# Nuio_Left_Keyboard_Rev_H_Power.net
KiCad netlist of a schematic drawn in Altium Designer
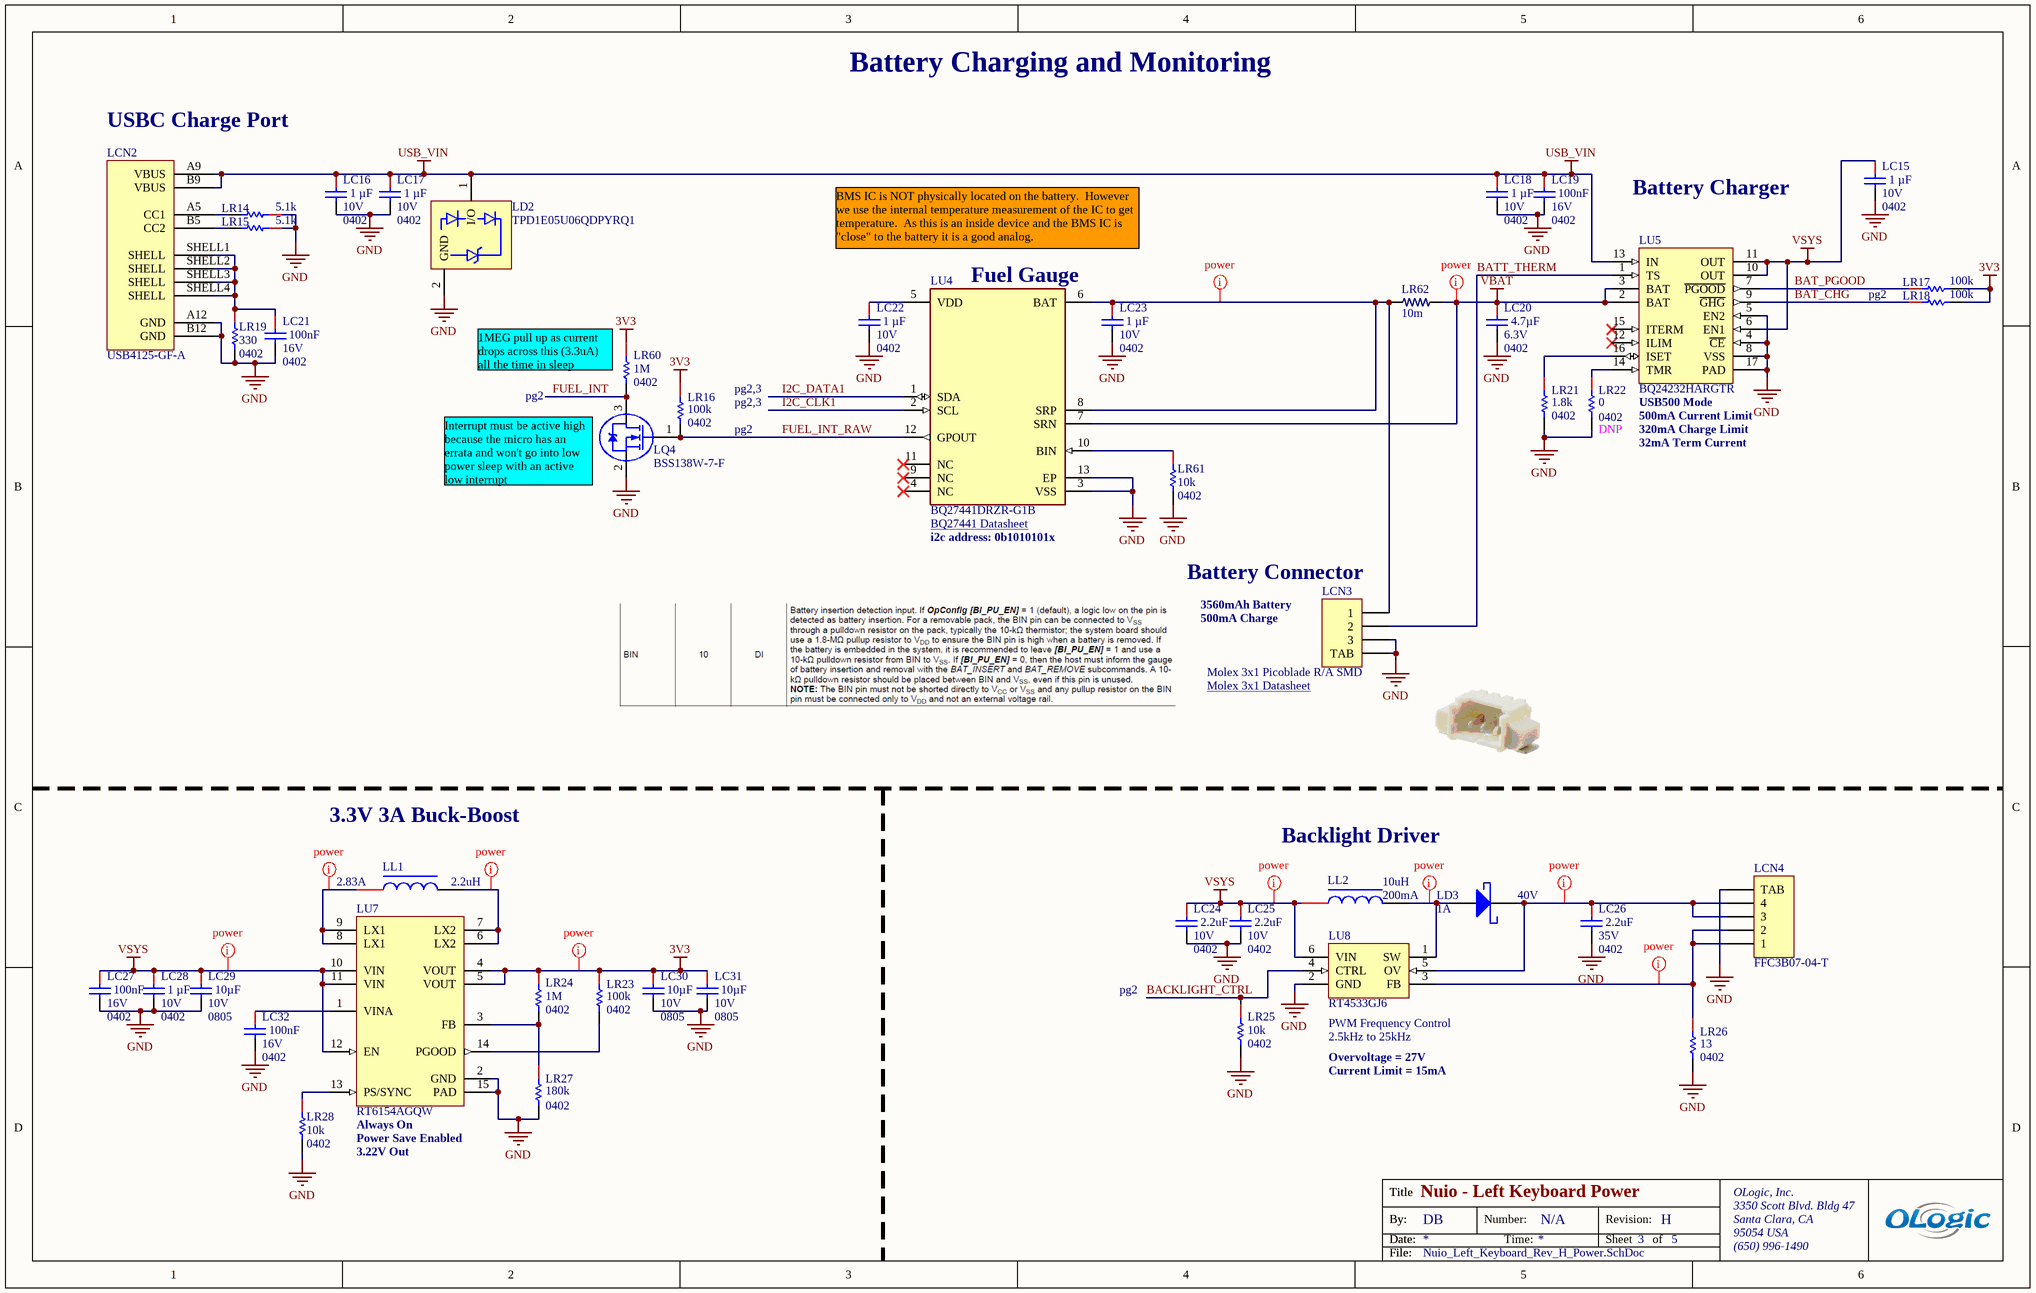
[diagram p0: Nuio_Left_Keyboard_Rev_H_Power.SchDoc]

(export (version "E")
  (design (tool "Eeschema 10.0.6"))
  (components
    (comp (ref "LC15")
      (value "CAP CER 1UF 10V X5R 0402")
      (footprint "CAPC0402(1005)_L")
      (description "±20% 10V Ceramic Capacitor X5R 0402 (1005 Metric)")
      (fields
        (field (name "PACKAGE (IMPERIAL)") "0402")
        (field (name "VOLTAGE (RATED)") "10V")
        (field (name "CAPACITANCE") "1 µF")
        (field (name "MANUFACTURER PART NUMBER") "CC0402MRX5R6BB105")
        (field (name "TOLERANCE") "±20%")
      )
      (libsource (lib "OLogic Nexus Vault") (part "OL_Capacitor"))
    )
    (comp (ref "LC16")
      (value "CAP CER 1UF 10V X5R 0402")
      (footprint "CAPC0402(1005)_L")
      (description "±20% 10V Ceramic Capacitor X5R 0402 (1005 Metric)")
      (fields
        (field (name "PACKAGE (IMPERIAL)") "0402")
        (field (name "VOLTAGE (RATED)") "10V")
        (field (name "CAPACITANCE") "1 µF")
        (field (name "MANUFACTURER PART NUMBER") "CC0402MRX5R6BB105")
        (field (name "TOLERANCE") "±20%")
      )
      (libsource (lib "OLogic Nexus Vault") (part "OL_Capacitor"))
    )
    (comp (ref "LC17")
      (value "CAP CER 1UF 10V X5R 0402")
      (footprint "CAPC0402(1005)_L")
      (description "±20% 10V Ceramic Capacitor X5R 0402 (1005 Metric)")
      (fields
        (field (name "PACKAGE (IMPERIAL)") "0402")
        (field (name "VOLTAGE (RATED)") "10V")
        (field (name "CAPACITANCE") "1 µF")
        (field (name "MANUFACTURER PART NUMBER") "CC0402MRX5R6BB105")
        (field (name "TOLERANCE") "±20%")
      )
      (libsource (lib "OLogic Nexus Vault") (part "OL_Capacitor"))
    )
    (comp (ref "LC18")
      (value "CAP CER 1UF 10V X5R 0402")
      (footprint "CAPC0402(1005)_L")
      (description "±20% 10V Ceramic Capacitor X5R 0402 (1005 Metric)")
      (fields
        (field (name "PACKAGE (IMPERIAL)") "0402")
        (field (name "VOLTAGE (RATED)") "10V")
        (field (name "CAPACITANCE") "1 µF")
        (field (name "MANUFACTURER PART NUMBER") "CC0402MRX5R6BB105")
        (field (name "TOLERANCE") "±20%")
      )
      (libsource (lib "OLogic Nexus Vault") (part "OL_Capacitor"))
    )
    (comp (ref "LC19")
      (value "CAP CER 0.1UF 16V X5R 0402")
      (footprint "CAPC0402(1005)_L")
      (description "±10% 16V Ceramic Capacitor X5R 0402 (1005 Metric)")
      (fields
        (field (name "PACKAGE (IMPERIAL)") "0402")
        (field (name "VOLTAGE (RATED)") "16V")
        (field (name "CAPACITANCE") "100nF")
        (field (name "MANUFACTURER") "Taiyo Yuden")
        (field (name "MANUFACTURER PART NUMBER") "EMK105BJ104KV-F")
      )
      (libsource (lib "OLogic Nexus Vault") (part "OL_Capacitor"))
    )
    (comp (ref "LC20")
      (value "4.7uF")
      (footprint "CAPC0402(1005)_L")
      (description "CAP CER 4.7UF 6.3V 10% X5R 0402")
      (fields
        (field (name "PACKAGE (IMPERIAL)") "0402")
        (field (name "VOLTAGE (RATED)") "6.3V")
        (field (name "CAPACITANCE") "4.7µF")
        (field (name "TOLERANCE") "20%")
      )
      (libsource (lib "OLogic Nexus Vault") (part "OL_Capacitor"))
    )
    (comp (ref "LC21")
      (value "CAP CER 0.1UF 16V X5R 0402")
      (footprint "CAPC0402(1005)_L")
      (description "±10% 16V Ceramic Capacitor X5R 0402 (1005 Metric)")
      (fields
        (field (name "PACKAGE (IMPERIAL)") "0402")
        (field (name "VOLTAGE (RATED)") "16V")
        (field (name "CAPACITANCE") "100nF")
        (field (name "MANUFACTURER") "Taiyo Yuden")
        (field (name "MANUFACTURER PART NUMBER") "EMK105BJ104KV-F")
      )
      (libsource (lib "OLogic Nexus Vault") (part "OL_Capacitor"))
    )
    (comp (ref "LC22")
      (value "CAP CER 1UF 10V X5R 0402")
      (footprint "CAPC0402(1005)_L")
      (description "±20% 10V Ceramic Capacitor X5R 0402 (1005 Metric)")
      (fields
        (field (name "PACKAGE (IMPERIAL)") "0402")
        (field (name "VOLTAGE (RATED)") "10V")
        (field (name "CAPACITANCE") "1 µF")
        (field (name "MANUFACTURER PART NUMBER") "CC0402MRX5R6BB105")
        (field (name "TOLERANCE") "±20%")
      )
      (libsource (lib "OLogic Nexus Vault") (part "OL_Capacitor"))
    )
    (comp (ref "LC23")
      (value "CAP CER 1UF 10V X5R 0402")
      (footprint "CAPC0402(1005)_L")
      (description "±20% 10V Ceramic Capacitor X5R 0402 (1005 Metric)")
      (fields
        (field (name "PACKAGE (IMPERIAL)") "0402")
        (field (name "VOLTAGE (RATED)") "10V")
        (field (name "CAPACITANCE") "1 µF")
        (field (name "MANUFACTURER PART NUMBER") "CC0402MRX5R6BB105")
        (field (name "TOLERANCE") "±20%")
      )
      (libsource (lib "OLogic Nexus Vault") (part "OL_Capacitor"))
    )
    (comp (ref "LC24")
      (value "CAP CER 2.2UF 10V X5R 0402")
      (footprint "CAPC0402(1005)_L")
      (description "±20% 10V Ceramic Capacitor X5R 0402 (1005 Metric)")
      (fields
        (field (name "PACKAGE (IMPERIAL)") "0402")
        (field (name "VOLTAGE (RATED)") "10V")
        (field (name "CAPACITANCE") "2.2uF")
        (field (name "TOLERANCE") "20%")
        (field (name "MANUFACTURER") "KEMET")
      )
      (libsource (lib "OLogic Nexus Vault") (part "OL_Capacitor"))
    )
    (comp (ref "LC25")
      (value "CAP CER 2.2UF 10V X5R 0402")
      (footprint "CAPC0402(1005)_L")
      (description "±20% 10V Ceramic Capacitor X5R 0402 (1005 Metric)")
      (fields
        (field (name "PACKAGE (IMPERIAL)") "0402")
        (field (name "VOLTAGE (RATED)") "10V")
        (field (name "CAPACITANCE") "2.2uF")
        (field (name "TOLERANCE") "20%")
        (field (name "MANUFACTURER") "KEMET")
      )
      (libsource (lib "OLogic Nexus Vault") (part "OL_Capacitor"))
    )
    (comp (ref "LC26")
      (value "2.2uF")
      (footprint "CAPC0402(1005)_L")
      (description "CAP CER 2.2UF 35V 10% X5R 0402")
      (fields
        (field (name "VOLTAGE (RATED)") "35V")
        (field (name "PACKAGE (IMPERIAL)") "0402")
        (field (name "TOLERANCE") "10%")
      )
      (libsource (lib "OLogic Nexus Vault") (part "=Capacitance"))
    )
    (comp (ref "LC27")
      (value "CAP CER 0.1UF 16V X5R 0402")
      (footprint "CAPC0402(1005)_L")
      (description "±10% 16V Ceramic Capacitor X5R 0402 (1005 Metric)")
      (fields
        (field (name "PACKAGE (IMPERIAL)") "0402")
        (field (name "VOLTAGE (RATED)") "16V")
        (field (name "CAPACITANCE") "100nF")
        (field (name "MANUFACTURER") "Taiyo Yuden")
        (field (name "MANUFACTURER PART NUMBER") "EMK105BJ104KV-F")
      )
      (libsource (lib "OLogic Nexus Vault") (part "OL_Capacitor"))
    )
    (comp (ref "LC28")
      (value "CAP CER 1UF 10V X5R 0402")
      (footprint "CAPC0402(1005)_L")
      (description "±20% 10V Ceramic Capacitor X5R 0402 (1005 Metric)")
      (fields
        (field (name "PACKAGE (IMPERIAL)") "0402")
        (field (name "VOLTAGE (RATED)") "10V")
        (field (name "CAPACITANCE") "1 µF")
        (field (name "MANUFACTURER PART NUMBER") "CC0402MRX5R6BB105")
        (field (name "TOLERANCE") "±20%")
      )
      (libsource (lib "OLogic Nexus Vault") (part "OL_Capacitor"))
    )
    (comp (ref "LC29")
      (value "CAP CER 10UF 10V X7R 0805")
      (footprint "CAPC0805(2012)_L")
      (description "10µF ±10% 10V Ceramic Capacitor X7R 0805 (2012 Metric)")
      (fields
        (field (name "VOLTAGE (RATED)") "10V")
        (field (name "PACKAGE (IMPERIAL)") "0805")
        (field (name "CAPACITANCE") "10µF")
        (field (name "TOLERANCE") "10%")
        (field (name "MANUFACTURER PART NUMBER") "GRM21BR71A106KA73K")
      )
      (libsource (lib "OLogic Nexus Vault") (part "OL_Capacitor"))
    )
    (comp (ref "LC30")
      (value "CAP CER 10UF 10V X7R 0805")
      (footprint "CAPC0805(2012)_L")
      (description "10µF ±10% 10V Ceramic Capacitor X7R 0805 (2012 Metric)")
      (fields
        (field (name "VOLTAGE (RATED)") "10V")
        (field (name "PACKAGE (IMPERIAL)") "0805")
        (field (name "CAPACITANCE") "10µF")
        (field (name "TOLERANCE") "10%")
        (field (name "MANUFACTURER PART NUMBER") "GRM21BR71A106KA73K")
      )
      (libsource (lib "OLogic Nexus Vault") (part "OL_Capacitor"))
    )
    (comp (ref "LC31")
      (value "CAP CER 10UF 10V X7R 0805")
      (footprint "CAPC0805(2012)_L")
      (description "10µF ±10% 10V Ceramic Capacitor X7R 0805 (2012 Metric)")
      (fields
        (field (name "VOLTAGE (RATED)") "10V")
        (field (name "PACKAGE (IMPERIAL)") "0805")
        (field (name "CAPACITANCE") "10µF")
        (field (name "TOLERANCE") "10%")
        (field (name "MANUFACTURER PART NUMBER") "GRM21BR71A106KA73K")
      )
      (libsource (lib "OLogic Nexus Vault") (part "OL_Capacitor"))
    )
    (comp (ref "LC32")
      (value "CAP CER 0.1UF 16V X5R 0402")
      (footprint "CAPC0402(1005)_L")
      (description "±10% 16V Ceramic Capacitor X5R 0402 (1005 Metric)")
      (fields
        (field (name "PACKAGE (IMPERIAL)") "0402")
        (field (name "VOLTAGE (RATED)") "16V")
        (field (name "CAPACITANCE") "100nF")
        (field (name "MANUFACTURER") "Taiyo Yuden")
        (field (name "MANUFACTURER PART NUMBER") "EMK105BJ104KV-F")
      )
      (libsource (lib "OLogic Nexus Vault") (part "OL_Capacitor"))
    )
    (comp (ref "LCN2")
      (value "USB4125-GF-A")
      (footprint "USB4125-GF-A")
      (fields (field (name "MANUFACTURER") "GCT") (field (name "VOLTAGE") "20V"))
      (libsource (lib "OLogic Nexus Vault") (part "USB4125-GF-A"))
    )
    (comp (ref "LCN3")
      (value "Molex 3x1 Picoblade R/A SMD")
      (footprint "Molex 3x1 Picoblade R_A SMD")
      (description "1.25mm (.049\") Pitch PicoBlade Header, Surface Mount, Right Angle, Lead-free, 3 Circuits")
      (libsource (lib "Nuio_Left_Keyboard_Rev_G") (part "CMP-00344-01"))
    )
    (comp (ref "LCN4")
      (value "FFC3B07-04-T")
      (footprint "FFC3B07-04-T")
      (fields (field (name "MANUFACTURER") "GCT"))
      (libsource (lib "OLogic Nexus Vault") (part "FFC3B07-04-T"))
    )
    (comp (ref "LD2")
      (value "TPD1E05U06QDPYRQ1")
      (footprint "FP-DPY0002A-MFG")
      (description "TVS DIODE 5.5V 14V 2X1SON")
      (fields (field (name "MANUFACTURER") "Texas Instruments"))
      (libsource (lib "OLogic Nexus Vault") (part "TPD1E05U06QDPYRQ1"))
    )
    (comp (ref "LD3")
      (value "PMEG4010AESBYL")
      (footprint "PMEG4010AESBYL-Footprint-1")
      (description "DIODE SCHOTTKY 40V 1A SOD993")
      (fields (field (name "DC REVERSE VOLTAGE MAX") "40V") (field (name "CURRENT AVG RECTIFIED") "1A"))
      (libsource (lib "OLogic Nexus Vault") (part "PMEG4010AESB"))
    )
    (comp (ref "LL1")
      (value "FIXED IND 2.2UH 2.83A 74MOHM SMD")
      (footprint "FIXED IND 2.2UH 2.83A 74MOHM SMD")
      (description "2.2 µH Shielded Wirewound Inductor 2.83 A 74mOhm Max Nonstandard -")
      (fields
        (field (name "INDUCTANCE") "2.2uH")
        (field (name "CURRENT RATING (AMPS)") "2.83A")
        (field (name "MANUFACTURER") "TDK Corporation")
      )
      (libsource (lib "OLogic Nexus Vault") (part "OL_Inductor"))
    )
    (comp (ref "LL2")
      (value "10uH")
      (footprint "FIXED IND 10UH 300MA 680MOHM SMD")
      (description "10 µH Shielded Multilayer Inductor 300 mA 680mOhm 0805 (2012 Metric)")
      (fields
        (field (name "MANUFACTURER PART NUMBER") "MLZ2012M100HT000")
        (field (name "TOLERANCE") "20%")
        (field (name "SATURATION CURRENT") "200mA")
      )
      (libsource (lib "OLogic Nexus Vault") (part "OL_Inductor"))
    )
    (comp (ref "LQ4")
      (value "BSS138W-7-F")
      (footprint "DIOD-SOT323-3_V")
      (description "DIODES INC. - BSS138W-7-F. - BSS FAMILY SOT323 T&R 3K ROHS COMPLIANT: YES")
      (fields (field (name "VOLTAGE") "50V") (field (name "POWER") "200mW"))
      (libsource (lib "Nuio_Left_Keyboard_Rev_H") (part "CMP-00300-01"))
    )
    (comp (ref "LR14")
      (value "RES SMD 5.1K OHM 1% 1/10W 0402")
      (footprint "RESC0402(1005)_L")
      (description "5.1 kOhms ±1% 0.1W, 1/10W Chip Resistor 0402 (1005 Metric) Automotive AEC-Q200 Thick Film")
      (fields
        (field (name "RESISTANCE") "5.1k")
        (field (name "POWER") "63mW")
        (field (name "TOLERANCE") "1%")
      )
      (libsource (lib "OLogic Nexus Vault") (part "=Resistance"))
    )
    (comp (ref "LR15")
      (value "RES SMD 5.1K OHM 1% 1/10W 0402")
      (footprint "RESC0402(1005)_L")
      (description "5.1 kOhms ±1% 0.1W, 1/10W Chip Resistor 0402 (1005 Metric) Automotive AEC-Q200 Thick Film")
      (fields
        (field (name "RESISTANCE") "5.1k")
        (field (name "POWER") "63mW")
        (field (name "TOLERANCE") "1%")
      )
      (libsource (lib "OLogic Nexus Vault") (part "=Resistance"))
    )
    (comp (ref "LR16")
      (value "100k")
      (footprint "RESC0402(1005)_L")
      (description "±1% 0.063W, 1/16W Chip Resistor 0402 (1005 Metric) Moisture Resistant Thick Film")
      (fields
        (field (name "CASE CODE (IMPERIAL)") "0402")
        (field (name "TOLERANCE") "1%")
        (field (name "MANUFACTURER") "YAGEO")
      )
      (libsource (lib "OLogic Nexus Vault") (part "=Resistance"))
    )
    (comp (ref "LR17")
      (value "100k")
      (footprint "RESC0402(1005)_L")
      (description "±1% 0.063W, 1/16W Chip Resistor 0402 (1005 Metric) Moisture Resistant Thick Film")
      (fields (field (name "TOLERANCE") "1%") (field (name "MANUFACTURER") "YAGEO"))
      (libsource (lib "OLogic Nexus Vault") (part "=Resistance"))
    )
    (comp (ref "LR18")
      (value "100k")
      (footprint "RESC0402(1005)_L")
      (description "±1% 0.063W, 1/16W Chip Resistor 0402 (1005 Metric) Moisture Resistant Thick Film")
      (fields (field (name "TOLERANCE") "1%") (field (name "MANUFACTURER") "YAGEO"))
      (libsource (lib "OLogic Nexus Vault") (part "=Resistance"))
    )
    (comp (ref "LR19")
      (value "RES SMD 330 OHM 1% 1/16W 0402")
      (footprint "RESC0402(1005)_L")
      (description "330 Ohms ±1% 0.063W, 1/16W Chip Resistor 0402 (1005 Metric) Automotive AEC-Q200 Thick Film")
      (fields
        (field (name "RESISTANCE") "330")
        (field (name "PACKAGE (IMPERIAL)") "0402")
        (field (name "POWER") "63mW")
        (field (name "TOLERANCE") "1%")
      )
      (libsource (lib "OLogic Nexus Vault") (part "OL_Resistor"))
    )
    (comp (ref "LR21")
      (value "1.8k")
      (footprint "RESC0402(1005)_L")
      (description "1.8 kOhms ±0.1% 0.063W, 1/16W Chip Resistor 0402 (1005 Metric) Automotive AEC-Q200 Thin Film")
      (fields
        (field (name "TOLERANCE") "0.1%")
        (field (name "CASE CODE (IMPERIAL)") "0402")
        (field (name "MANUFACTURER") "Panasonic Electronic Components")
      )
      (libsource (lib "OLogic Nexus Vault") (part "=Resistance"))
    )
    (comp (ref "LR22")
      (value "RES 0 OHM JUMPER 1/16W 0402")
      (footprint "RESC0402(1005)_L")
      (description "0 Ohms Jumper Chip Resistor 0402 (1005 Metric) Automotive AEC-Q200 Thick Film")
      (fields
        (field (name "PACKAGE (IMPERIAL)") "0402")
        (field (name "RESISTANCE") "0")
        (field (name "POWER") "63mW")
        (field (name "TOLERANCE") "0%")
      )
      (libsource (lib "OLogic Nexus Vault") (part "=Resistance"))
    )
    (comp (ref "LR23")
      (value "100k")
      (footprint "RESC0402(1005)_L")
      (description "±1% 0.063W, 1/16W Chip Resistor 0402 (1005 Metric) Moisture Resistant Thick Film")
      (fields
        (field (name "CASE CODE (IMPERIAL)") "0402")
        (field (name "TOLERANCE") "1%")
        (field (name "MANUFACTURER") "YAGEO")
      )
      (libsource (lib "OLogic Nexus Vault") (part "=Resistance"))
    )
    (comp (ref "LR24")
      (value "RES 1M OHM 1% 1/16W 0402")
      (footprint "RESC0402(1005)_L")
      (description "1 MOhms ±1% 0.063W, 1/16W Chip Resistor 0402 (1005 Metric) Moisture Resistant Thick Film")
      (fields
        (field (name "RESISTANCE") "1M")
        (field (name "CASE/PACKAGE") "0402")
        (field (name "MANUFACTURER") "YAGEO")
        (field (name "MANUFACTURER PART NUMBER") "RC0402FR-071ML")
      )
      (libsource (lib "OLogic Nexus Vault") (part "OL_Resistor"))
    )
    (comp (ref "LR25")
      (value "RES SMD 10K OHM 1% 1/16W 0402")
      (footprint "RESC0402_YAGEO")
      (fields
        (field (name "RESISTANCE") "10k")
        (field (name "PACKAGE (IMPERIAL)") "0402")
        (field (name "MANUFACTURER") "Yageo")
        (field (name "TOLERANCE") "1%")
        (field (name "MANUFACTURER PART NUMBER") "AT0402FRE0710KL")
      )
      (libsource (lib "OLogic Nexus Vault") (part "OL_Resistor"))
    )
    (comp (ref "LR26")
      (value "13")
      (footprint "RESC0402(1005)_L")
      (description "SMD Chip Resistor, 13 Ohm, ± 1%, 63 mW, 0402 [1005 Metric], Thick Film, General Purpose")
      (fields (field (name "TOLERANCE") "1%") (field (name "CASE/PACKAGE") "0402"))
      (libsource (lib "Nuio_Left_Keyboard_Rev_G") (part "CMP-001-2304-01"))
    )
    (comp (ref "LR27")
      (value "180k")
      (footprint "RESC0402(1005)_L")
      (description "RES 180K OHM 1% 1/16W 0402")
      (fields
        (field (name "PACKAGE (IMPERIAL)") "0402")
        (field (name "POWER") "63mW")
        (field (name "TOLERANCE") "1%")
        (field (name "RESISTANCE") "180k")
      )
      (libsource (lib "OLogic Nexus Vault") (part "=Resistance"))
    )
    (comp (ref "LR28")
      (value "RES SMD 10K OHM 1% 1/16W 0402")
      (footprint "RESC0402_YAGEO")
      (fields
        (field (name "RESISTANCE") "10k")
        (field (name "PACKAGE (IMPERIAL)") "0402")
        (field (name "MANUFACTURER") "Yageo")
        (field (name "TOLERANCE") "1%")
        (field (name "MANUFACTURER PART NUMBER") "AT0402FRE0710KL")
      )
      (libsource (lib "OLogic Nexus Vault") (part "OL_Resistor"))
    )
    (comp (ref "LR60")
      (value "RES 1M OHM 1% 1/16W 0402")
      (footprint "RESC0402(1005)_L")
      (description "1 MOhms ±1% 0.063W, 1/16W Chip Resistor 0402 (1005 Metric) Moisture Resistant Thick Film")
      (fields
        (field (name "RESISTANCE") "1M")
        (field (name "CASE/PACKAGE") "0402")
        (field (name "MANUFACTURER") "YAGEO")
        (field (name "MANUFACTURER PART NUMBER") "RC0402FR-071ML")
      )
      (libsource (lib "OLogic Nexus Vault") (part "OL_Resistor"))
    )
    (comp (ref "LR61")
      (value "RES SMD 10K OHM 1% 1/16W 0402")
      (footprint "RESC0402_YAGEO")
      (fields
        (field (name "RESISTANCE") "10k")
        (field (name "PACKAGE (IMPERIAL)") "0402")
        (field (name "MANUFACTURER") "Yageo")
        (field (name "TOLERANCE") "1%")
        (field (name "MANUFACTURER PART NUMBER") "AT0402FRE0710KL")
      )
      (libsource (lib "OLogic Nexus Vault") (part "OL_Resistor"))
    )
    (comp (ref "LR62")
      (value "10m")
      (footprint "0805 PACKAGE")
      (description "10mOhm 0805 Resistor 1%")
      (libsource (lib "Resistor 0805 1P") (part "10m 0805 Resistor 1%_1"))
    )
    (comp (ref "LU4")
      (value "BQ27441DRZR-G1B")
      (footprint "Nuio_Left_Keyboard_Rev_H:FP-DRZ0012A-MFG")
      (description "IC BATT FUEL GAUGE LI-ION 12SON")
      (libsource (lib "Nuio_Left_Keyboard_Rev_H") (part "CMP-04911-000067-1"))
    )
    (comp (ref "LU5")
      (value "BQ24232HARGTR")
      (footprint "BQ24232HARGTR")
      (description "USB Friendly 0.5A Li-ion charger with power-Path, 10.5V OVP 16-VQFN -5 to 125")
      (libsource (lib "Nuio_Left_Keyboard_Rev_G") (part "CMP-001-1983-03"))
    )
    (comp (ref "LU7")
      (value "RT6154AGQW")
      (footprint "PSON50P300X80_HS-15N")
      (description "IC REG BCK BST ADJ 4A 14WDFN")
      (fields (field (name "MANUFACTURER") "Richtek USA Inc."))
      (libsource (lib "OLogic Nexus Vault") (part "RT6154AGQW"))
    )
    (comp (ref "LU8")
      (value "RT4533GJ6")
      (footprint "RT4533GJ6")
      (description "IC LED DRVR RGLTR PWM TSOT23-6")
      (libsource (lib "OLogic Nexus Vault") (part "RT4533GJ6"))
    )
  )
  (nets
    (net (code "1") (name "/BACKLIGHT_CTRL") (class "Default")
      (node (ref "LR25") (pin "1") (pinfunction "1_1") (pintype "passive"))
      (node (ref "LU8") (pin "4") (pinfunction "CTRL_4") (pintype "input"))
    )
    (net (code "2") (name "/BATT_THERM") (class "Default")
      (node (ref "LCN3") (pin "2") (pinfunction "2_2") (pintype "passive"))
      (node (ref "LU5") (pin "1") (pinfunction "TS_1") (pintype "input"))
    )
    (net (code "3") (name "/BAT_CHG") (class "Default")
      (node (ref "LR18") (pin "1") (pinfunction "1_1") (pintype "passive"))
      (node (ref "LU5") (pin "9") (pinfunction "~{GHG}_9") (pintype "output"))
    )
    (net (code "4") (name "/BAT_PGOOD") (class "Default")
      (node (ref "LR17") (pin "1") (pinfunction "1_1") (pintype "passive"))
      (node (ref "LU5") (pin "7") (pinfunction "~{PGOOD}_7") (pintype "output"))
    )
    (net (code "5") (name "/FUEL_INT") (class "Default")
      (node (ref "LQ4") (pin "3") (pinfunction "D_3") (pintype "passive"))
      (node (ref "LR60") (pin "2") (pinfunction "2_2") (pintype "passive"))
    )
    (net (code "6") (name "/FUEL_INT_RAW") (class "Default")
      (node (ref "LQ4") (pin "1") (pinfunction "G_1") (pintype "passive"))
      (node (ref "LR16") (pin "2") (pinfunction "2_2") (pintype "passive"))
      (node (ref "LU4") (pin "12") (pinfunction "GPOUT_12") (pintype "output"))
    )
    (net (code "7") (name "/I2C_CLK1") (class "Default")
      (node (ref "LU4") (pin "2") (pinfunction "SCL_2") (pintype "input"))
    )
    (net (code "8") (name "/I2C_DATA1") (class "Default")
      (node (ref "LU4") (pin "1") (pinfunction "SDA_1") (pintype "bidirectional"))
    )
    (net (code "9") (name "3V3") (class "Default")
      (node (ref "LC30") (pin "1") (pinfunction "1_1") (pintype "passive"))
      (node (ref "LC31") (pin "1") (pinfunction "1_1") (pintype "passive"))
      (node (ref "LR16") (pin "1") (pinfunction "1_1") (pintype "passive"))
      (node (ref "LR17") (pin "2") (pinfunction "2_2") (pintype "passive"))
      (node (ref "LR18") (pin "2") (pinfunction "2_2") (pintype "passive"))
      (node (ref "LR23") (pin "1") (pinfunction "1_1") (pintype "passive"))
      (node (ref "LR24") (pin "1") (pinfunction "1_1") (pintype "passive"))
      (node (ref "LR60") (pin "1") (pinfunction "1_1") (pintype "passive"))
      (node (ref "LU7") (pin "4") (pinfunction "VOUT_4") (pintype "power_in"))
      (node (ref "LU7") (pin "5") (pinfunction "VOUT_5") (pintype "power_in"))
    )
    (net (code "10") (name "GND") (class "Default")
      (node (ref "LC15") (pin "2") (pinfunction "2_2") (pintype "passive"))
      (node (ref "LC16") (pin "2") (pinfunction "2_2") (pintype "passive"))
      (node (ref "LC17") (pin "2") (pinfunction "2_2") (pintype "passive"))
      (node (ref "LC18") (pin "2") (pinfunction "2_2") (pintype "passive"))
      (node (ref "LC19") (pin "2") (pinfunction "2_2") (pintype "passive"))
      (node (ref "LC20") (pin "2") (pinfunction "2_2") (pintype "passive"))
      (node (ref "LC21") (pin "2") (pinfunction "2_2") (pintype "passive"))
      (node (ref "LC22") (pin "2") (pinfunction "2_2") (pintype "passive"))
      (node (ref "LC23") (pin "2") (pinfunction "2_2") (pintype "passive"))
      (node (ref "LC24") (pin "2") (pinfunction "2_2") (pintype "passive"))
      (node (ref "LC25") (pin "2") (pinfunction "2_2") (pintype "passive"))
      (node (ref "LC26") (pin "2") (pinfunction "2_2") (pintype "passive"))
      (node (ref "LC27") (pin "2") (pinfunction "2_2") (pintype "passive"))
      (node (ref "LC28") (pin "2") (pinfunction "2_2") (pintype "passive"))
      (node (ref "LC29") (pin "2") (pinfunction "2_2") (pintype "passive"))
      (node (ref "LC30") (pin "2") (pinfunction "2_2") (pintype "passive"))
      (node (ref "LC31") (pin "2") (pinfunction "2_2") (pintype "passive"))
      (node (ref "LC32") (pin "2") (pinfunction "2_2") (pintype "passive"))
      (node (ref "LCN2") (pin "A12") (pinfunction "GND_A12") (pintype "passive"))
      (node (ref "LCN2") (pin "B12") (pinfunction "GND_B12") (pintype "passive"))
      (node (ref "LCN3") (pin "0") (pinfunction "TAB_0") (pintype "passive"))
      (node (ref "LCN3") (pin "3") (pinfunction "3_3") (pintype "passive"))
      (node (ref "LCN4") (pin "0") (pinfunction "TAB_0") (pintype "passive"))
      (node (ref "LD2") (pin "2") (pinfunction "GND_2") (pintype "passive"))
      (node (ref "LQ4") (pin "2") (pinfunction "S_2") (pintype "passive"))
      (node (ref "LR14") (pin "1") (pinfunction "1_1") (pintype "passive"))
      (node (ref "LR15") (pin "1") (pinfunction "1_1") (pintype "passive"))
      (node (ref "LR19") (pin "2") (pinfunction "2_2") (pintype "passive"))
      (node (ref "LR21") (pin "2") (pinfunction "2_2") (pintype "passive"))
      (node (ref "LR22") (pin "2") (pinfunction "2_2") (pintype "passive"))
      (node (ref "LR25") (pin "2") (pinfunction "2_2") (pintype "passive"))
      (node (ref "LR26") (pin "2") (pinfunction "2_2") (pintype "passive"))
      (node (ref "LR27") (pin "2") (pinfunction "2_2") (pintype "passive"))
      (node (ref "LR28") (pin "2") (pinfunction "2_2") (pintype "passive"))
      (node (ref "LR61") (pin "2") (pinfunction "2_2") (pintype "passive"))
      (node (ref "LU4") (pin "13") (pinfunction "EP_13") (pintype "passive"))
      (node (ref "LU4") (pin "3") (pinfunction "VSS_3") (pintype "power_in"))
      (node (ref "LU5") (pin "17") (pinfunction "PAD_17") (pintype "passive"))
      (node (ref "LU5") (pin "4") (pinfunction "~{CE}_4") (pintype "input"))
      (node (ref "LU5") (pin "5") (pinfunction "EN2_5") (pintype "input"))
      (node (ref "LU5") (pin "8") (pinfunction "VSS_8") (pintype "passive"))
      (node (ref "LU7") (pin "15") (pinfunction "PAD_15") (pintype "power_in"))
      (node (ref "LU7") (pin "2") (pinfunction "GND_2") (pintype "power_in"))
      (node (ref "LU8") (pin "2") (pinfunction "GND_2") (pintype "power_in"))
    )
    (net (code "11") (name "Net-(LC21-Pad1)") (class "Default")
      (node (ref "LC21") (pin "1") (pinfunction "1_1") (pintype "passive"))
      (node (ref "LCN2") (pin "SHELL1") (pinfunction "SHELL_SHELL1") (pintype "passive"))
      (node (ref "LCN2") (pin "SHELL2") (pinfunction "SHELL_SHELL2") (pintype "passive"))
      (node (ref "LCN2") (pin "SHELL3") (pinfunction "SHELL_SHELL3") (pintype "passive"))
      (node (ref "LCN2") (pin "SHELL4") (pinfunction "SHELL_SHELL4") (pintype "passive"))
      (node (ref "LR19") (pin "1") (pinfunction "1_1") (pintype "passive"))
    )
    (net (code "12") (name "Net-(LCN2-CC1)") (class "Default")
      (node (ref "LCN2") (pin "A5") (pinfunction "CC1_A5") (pintype "passive"))
      (node (ref "LR14") (pin "2") (pinfunction "2_2") (pintype "passive"))
    )
    (net (code "13") (name "Net-(LCN2-CC2)") (class "Default")
      (node (ref "LCN2") (pin "B5") (pinfunction "CC2_B5") (pintype "passive"))
      (node (ref "LR15") (pin "2") (pinfunction "2_2") (pintype "passive"))
    )
    (net (code "14") (name "Net-(LD3-A)") (class "Default")
      (node (ref "LD3") (pin "2") (pinfunction "A_2") (pintype "passive"))
      (node (ref "LL2") (pin "2") (pinfunction "2_2") (pintype "passive"))
      (node (ref "LU8") (pin "1") (pinfunction "SW_1") (pintype "passive"))
    )
    (net (code "15") (name "Net-(LD3-K)") (class "Default")
      (node (ref "LC26") (pin "1") (pinfunction "1_1") (pintype "passive"))
      (node (ref "LCN4") (pin "3") (pinfunction "3_3") (pintype "passive"))
      (node (ref "LCN4") (pin "4") (pinfunction "4_4") (pintype "passive"))
      (node (ref "LD3") (pin "1") (pinfunction "K_1") (pintype "passive"))
      (node (ref "LU8") (pin "5") (pinfunction "OV_5") (pintype "input"))
    )
    (net (code "16") (name "Net-(LL1-Pad1)") (class "Default")
      (node (ref "LL1") (pin "1") (pinfunction "1_1") (pintype "passive"))
      (node (ref "LU7") (pin "8") (pinfunction "LX1_8") (pintype "passive"))
      (node (ref "LU7") (pin "9") (pinfunction "LX1_9") (pintype "passive"))
    )
    (net (code "17") (name "Net-(LL1-Pad2)") (class "Default")
      (node (ref "LL1") (pin "2") (pinfunction "2_2") (pintype "passive"))
      (node (ref "LU7") (pin "6") (pinfunction "LX2_6") (pintype "passive"))
      (node (ref "LU7") (pin "7") (pinfunction "LX2_7") (pintype "passive"))
    )
    (net (code "18") (name "Net-(LU4-BAT)") (class "Default")
      (node (ref "LC23") (pin "1") (pinfunction "1_1") (pintype "passive"))
      (node (ref "LCN3") (pin "1") (pinfunction "1_1") (pintype "passive"))
      (node (ref "LR62") (pin "1") (pinfunction "1_1") (pintype "passive"))
      (node (ref "LU4") (pin "6") (pinfunction "BAT_6") (pintype "power_in"))
      (node (ref "LU4") (pin "8") (pinfunction "SRP_8") (pintype "passive"))
    )
    (net (code "19") (name "Net-(LU4-BIN)") (class "Default")
      (node (ref "LR61") (pin "1") (pinfunction "1_1") (pintype "passive"))
      (node (ref "LU4") (pin "10") (pinfunction "BIN_10") (pintype "input"))
    )
    (net (code "20") (name "Net-(LU4-VDD)") (class "Default")
      (node (ref "LC22") (pin "1") (pinfunction "1_1") (pintype "passive"))
      (node (ref "LU4") (pin "5") (pinfunction "VDD_5") (pintype "power_in"))
    )
    (net (code "21") (name "Net-(LU5-ISET)") (class "Default")
      (node (ref "LR21") (pin "1") (pinfunction "1_1") (pintype "passive"))
      (node (ref "LU5") (pin "16") (pinfunction "ISET_16") (pintype "bidirectional"))
    )
    (net (code "22") (name "Net-(LU5-TMR)") (class "Default")
      (node (ref "LR22") (pin "1") (pinfunction "1_1") (pintype "passive"))
      (node (ref "LU5") (pin "14") (pinfunction "TMR_14") (pintype "input"))
    )
    (net (code "23") (name "Net-(LU7-FB)") (class "Default")
      (node (ref "LR24") (pin "2") (pinfunction "2_2") (pintype "passive"))
      (node (ref "LR27") (pin "1") (pinfunction "1_1") (pintype "passive"))
      (node (ref "LU7") (pin "3") (pinfunction "FB_3") (pintype "passive"))
    )
    (net (code "24") (name "Net-(LU7-PGOOD)") (class "Default")
      (node (ref "LR23") (pin "2") (pinfunction "2_2") (pintype "passive"))
      (node (ref "LU7") (pin "14") (pinfunction "PGOOD_14") (pintype "output"))
    )
    (net (code "25") (name "Net-(LU7-PS{slash}SYNC)") (class "Default")
      (node (ref "LR28") (pin "1") (pinfunction "1_1") (pintype "passive"))
      (node (ref "LU7") (pin "13") (pinfunction "PS/SYNC_13") (pintype "input"))
    )
    (net (code "26") (name "Net-(LU7-VINA)") (class "Default")
      (node (ref "LC32") (pin "1") (pinfunction "1_1") (pintype "passive"))
      (node (ref "LU7") (pin "1") (pinfunction "VINA_1") (pintype "power_in"))
    )
    (net (code "27") (name "Net-(LU8-FB)") (class "Default")
      (node (ref "LCN4") (pin "1") (pinfunction "1_1") (pintype "passive"))
      (node (ref "LCN4") (pin "2") (pinfunction "2_2") (pintype "passive"))
      (node (ref "LR26") (pin "1") (pinfunction "1_1") (pintype "passive"))
      (node (ref "LU8") (pin "3") (pinfunction "FB_3") (pintype "passive"))
    )
    (net (code "28") (name "USB_VIN") (class "Default")
      (node (ref "LC16") (pin "1") (pinfunction "1_1") (pintype "passive"))
      (node (ref "LC17") (pin "1") (pinfunction "1_1") (pintype "passive"))
      (node (ref "LC18") (pin "1") (pinfunction "1_1") (pintype "passive"))
      (node (ref "LC19") (pin "1") (pinfunction "1_1") (pintype "passive"))
      (node (ref "LCN2") (pin "A9") (pinfunction "VBUS_A9") (pintype "passive"))
      (node (ref "LCN2") (pin "B9") (pinfunction "VBUS_B9") (pintype "passive"))
      (node (ref "LD2") (pin "1") (pinfunction "I/O_1") (pintype "passive"))
      (node (ref "LU5") (pin "13") (pinfunction "IN_13") (pintype "input"))
    )
    (net (code "29") (name "VBAT") (class "Default")
      (node (ref "LC20") (pin "1") (pinfunction "1_1") (pintype "passive"))
      (node (ref "LR62") (pin "2") (pinfunction "2_2") (pintype "passive"))
      (node (ref "LU4") (pin "7") (pinfunction "SRN_7") (pintype "passive"))
      (node (ref "LU5") (pin "2") (pinfunction "BAT_2") (pintype "passive"))
      (node (ref "LU5") (pin "3") (pinfunction "BAT_3") (pintype "passive"))
    )
    (net (code "30") (name "VSYS") (class "Default")
      (node (ref "LC15") (pin "1") (pinfunction "1_1") (pintype "passive"))
      (node (ref "LC24") (pin "1") (pinfunction "1_1") (pintype "passive"))
      (node (ref "LC25") (pin "1") (pinfunction "1_1") (pintype "passive"))
      (node (ref "LC27") (pin "1") (pinfunction "1_1") (pintype "passive"))
      (node (ref "LC28") (pin "1") (pinfunction "1_1") (pintype "passive"))
      (node (ref "LC29") (pin "1") (pinfunction "1_1") (pintype "passive"))
      (node (ref "LL2") (pin "1") (pinfunction "1_1") (pintype "passive"))
      (node (ref "LU5") (pin "10") (pinfunction "OUT_10") (pintype "passive"))
      (node (ref "LU5") (pin "11") (pinfunction "OUT_11") (pintype "passive"))
      (node (ref "LU5") (pin "6") (pinfunction "EN1_6") (pintype "input"))
      (node (ref "LU7") (pin "10") (pinfunction "VIN_10") (pintype "power_in"))
      (node (ref "LU7") (pin "11") (pinfunction "VIN_11") (pintype "power_in"))
      (node (ref "LU7") (pin "12") (pinfunction "EN_12") (pintype "input"))
      (node (ref "LU8") (pin "6") (pinfunction "VIN_6") (pintype "power_in"))
    )
    (net (code "31") (name "unconnected-(LU4-NC-Pad4)") (class "Default")
      (node (ref "LU4") (pin "4") (pinfunction "NC_4") (pintype "passive+no_connect"))
    )
    (net (code "32") (name "unconnected-(LU4-NC-Pad9)") (class "Default")
      (node (ref "LU4") (pin "9") (pinfunction "NC_9") (pintype "passive+no_connect"))
    )
    (net (code "33") (name "unconnected-(LU4-NC-Pad11)") (class "Default")
      (node (ref "LU4") (pin "11") (pinfunction "NC_11") (pintype "passive+no_connect"))
    )
    (net (code "34") (name "unconnected-(LU5-ILIM-Pad12)") (class "Default")
      (node (ref "LU5") (pin "12") (pinfunction "ILIM_12") (pintype "input+no_connect"))
    )
    (net (code "35") (name "unconnected-(LU5-ITERM-Pad15)") (class "Default")
      (node (ref "LU5") (pin "15") (pinfunction "ITERM_15") (pintype "input+no_connect"))
    )
  )
)
